# LED.net
KiCad netlist of a schematic drawn in Altium Designer
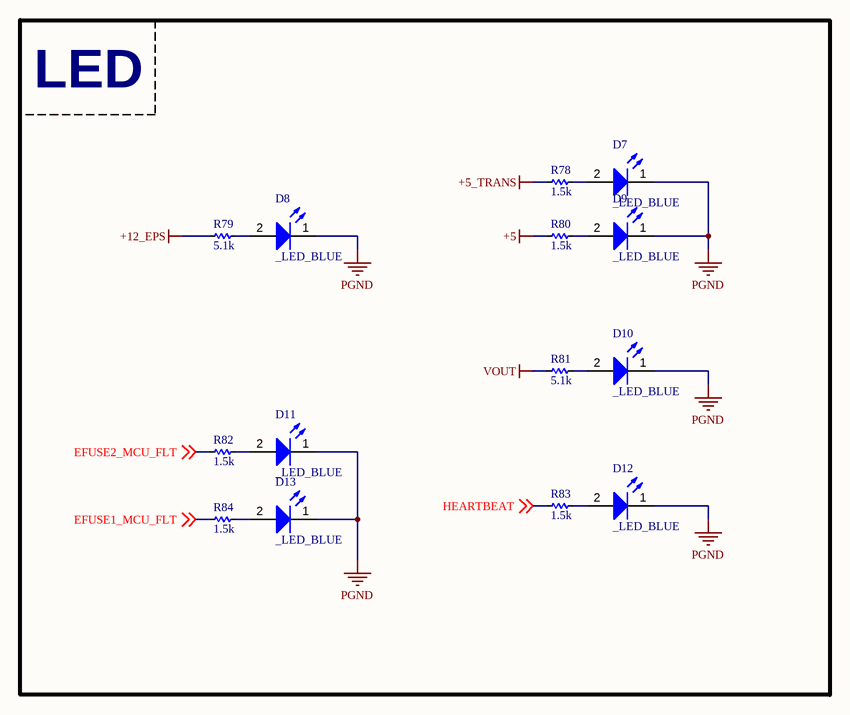
[diagram p0: LED.SchDoc]

(export (version "E")
  (design (tool "Eeschema 10.0.6"))
  (components
    (comp (ref "D7") (value "_LED_BLUE") (footprint "LED_0603") (libsource (lib "LABLIB") (part "_LED_BLUE")))
    (comp (ref "D8") (value "_LED_BLUE") (footprint "LED_0603") (libsource (lib "LABLIB") (part "_LED_BLUE")))
    (comp (ref "D9") (value "_LED_BLUE") (footprint "LED_0603") (libsource (lib "LABLIB") (part "_LED_BLUE")))
    (comp (ref "D10")
      (value "_LED_BLUE")
      (footprint "LED_0603")
      (libsource (lib "LABLIB") (part "_LED_BLUE"))
    )
    (comp (ref "D11")
      (value "_LED_BLUE")
      (footprint "LED_0603")
      (libsource (lib "LABLIB") (part "_LED_BLUE"))
    )
    (comp (ref "D12")
      (value "_LED_BLUE")
      (footprint "LED_0603")
      (libsource (lib "LABLIB") (part "_LED_BLUE"))
    )
    (comp (ref "D13")
      (value "_LED_BLUE")
      (footprint "LED_0603")
      (libsource (lib "LABLIB") (part "_LED_BLUE"))
    )
    (comp (ref "R78")
      (value "1.5k")
      (footprint "RES_C_1608X60")
      (description "RES")
      (libsource (lib "LABLIB") (part "_RES_B_2_2"))
    )
    (comp (ref "R79")
      (value "5.1k")
      (footprint "RES_C_1608X60")
      (description "RES")
      (libsource (lib "LABLIB") (part "_RES_B_2_2"))
    )
    (comp (ref "R80")
      (value "1.5k")
      (footprint "RES_C_1608X60")
      (description "RES")
      (libsource (lib "LABLIB") (part "_RES_B_2_2"))
    )
    (comp (ref "R81")
      (value "5.1k")
      (footprint "RES_C_1608X60")
      (description "RES")
      (libsource (lib "LABLIB") (part "_RES_B_2_2"))
    )
    (comp (ref "R82")
      (value "1.5k")
      (footprint "RES_C_1608X60")
      (description "RES")
      (libsource (lib "LABLIB") (part "_RES_B_2_2"))
    )
    (comp (ref "R83")
      (value "1.5k")
      (footprint "RES_C_1608X60")
      (description "RES")
      (libsource (lib "LABLIB") (part "_RES_B_2_2"))
    )
    (comp (ref "R84")
      (value "1.5k")
      (footprint "RES_C_1608X60")
      (description "RES")
      (libsource (lib "LABLIB") (part "_RES_B_2_2"))
    )
  )
  (nets
    (net (code "1") (name "+5") (class "Default")
      (node (ref "R80") (pin "2") (pinfunction "2_2") (pintype "passive"))
    )
    (net (code "2") (name "+5_TRANS") (class "Default")
      (node (ref "R78") (pin "2") (pinfunction "2_2") (pintype "passive"))
    )
    (net (code "3") (name "+12_EPS") (class "Default")
      (node (ref "R79") (pin "2") (pinfunction "2_2") (pintype "passive"))
    )
    (net (code "4") (name "EFUSE1_MCU_FLT") (class "Default")
      (node (ref "R84") (pin "2") (pinfunction "2_2") (pintype "passive"))
    )
    (net (code "5") (name "EFUSE2_MCU_FLT") (class "Default")
      (node (ref "R82") (pin "2") (pinfunction "2_2") (pintype "passive"))
    )
    (net (code "6") (name "HEARTBEAT") (class "Default")
      (node (ref "R83") (pin "2") (pinfunction "2_2") (pintype "passive"))
    )
    (net (code "7") (name "Net-(D7-A)") (class "Default")
      (node (ref "D7") (pin "2") (pinfunction "A_2") (pintype "passive"))
      (node (ref "R78") (pin "1") (pinfunction "1_1") (pintype "passive"))
    )
    (net (code "8") (name "Net-(D8-A)") (class "Default")
      (node (ref "D8") (pin "2") (pinfunction "A_2") (pintype "passive"))
      (node (ref "R79") (pin "1") (pinfunction "1_1") (pintype "passive"))
    )
    (net (code "9") (name "Net-(D9-A)") (class "Default")
      (node (ref "D9") (pin "2") (pinfunction "A_2") (pintype "passive"))
      (node (ref "R80") (pin "1") (pinfunction "1_1") (pintype "passive"))
    )
    (net (code "10") (name "Net-(D10-A)") (class "Default")
      (node (ref "D10") (pin "2") (pinfunction "A_2") (pintype "passive"))
      (node (ref "R81") (pin "1") (pinfunction "1_1") (pintype "passive"))
    )
    (net (code "11") (name "Net-(D11-A)") (class "Default")
      (node (ref "D11") (pin "2") (pinfunction "A_2") (pintype "passive"))
      (node (ref "R82") (pin "1") (pinfunction "1_1") (pintype "passive"))
    )
    (net (code "12") (name "Net-(D12-A)") (class "Default")
      (node (ref "D12") (pin "2") (pinfunction "A_2") (pintype "passive"))
      (node (ref "R83") (pin "1") (pinfunction "1_1") (pintype "passive"))
    )
    (net (code "13") (name "Net-(D13-A)") (class "Default")
      (node (ref "D13") (pin "2") (pinfunction "A_2") (pintype "passive"))
      (node (ref "R84") (pin "1") (pinfunction "1_1") (pintype "passive"))
    )
    (net (code "14") (name "PGND") (class "Default")
      (node (ref "D10") (pin "1") (pinfunction "K_1") (pintype "passive"))
      (node (ref "D11") (pin "1") (pinfunction "K_1") (pintype "passive"))
      (node (ref "D12") (pin "1") (pinfunction "K_1") (pintype "passive"))
      (node (ref "D13") (pin "1") (pinfunction "K_1") (pintype "passive"))
      (node (ref "D7") (pin "1") (pinfunction "K_1") (pintype "passive"))
      (node (ref "D8") (pin "1") (pinfunction "K_1") (pintype "passive"))
      (node (ref "D9") (pin "1") (pinfunction "K_1") (pintype "passive"))
    )
    (net (code "15") (name "VOUT") (class "Default")
      (node (ref "R81") (pin "2") (pinfunction "2_2") (pintype "passive"))
    )
  )
)
